# DC48V_DC24V_200W_V2_0.net
KiCad netlist of a schematic drawn in Altium Designer
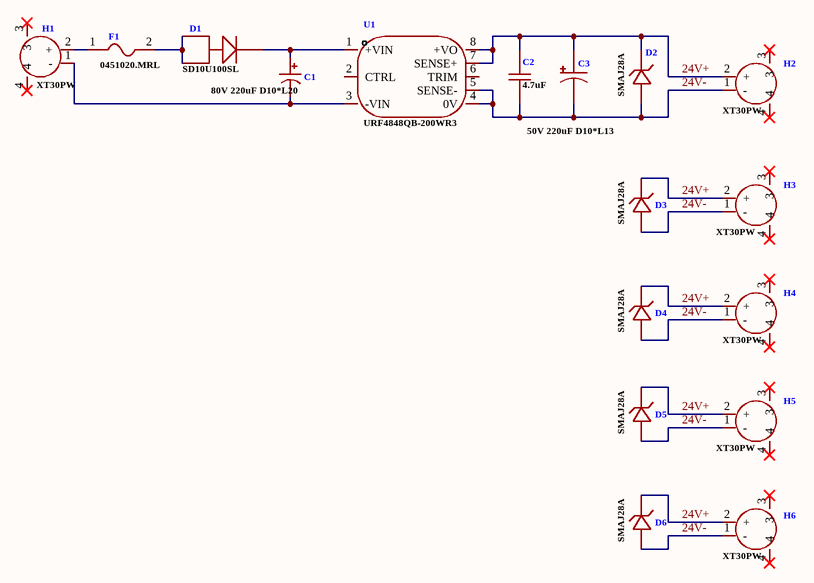
[diagram p0: DC48V_DC24V_200W_V2.0.SchDoc]

(export (version "E")
  (design (tool "Eeschema 10.0.6"))
  (components
    (comp (ref "C1")
      (value "80V 220uF D10*L20")
      (footprint "CAP-TH_BD10.0-P5.00-D1.0-FD-WL")
      (fields
        (field (name "MANUFACTURER") "AISHI(艾华集团)")
        (field (name "MANUFACTURER PART") "ERF1BM221G20OT")
        (field (name "TOLERANCE") "±20%")
      )
      (libsource (lib "电容") (part "ERF1BM221G20OT"))
    )
    (comp (ref "C2")
      (value "4.7uF")
      (footprint "1210_C")
      (description "100V 4.7uf 1210")
      (fields (field (name "MANUFACTURER") "FH(风华)") (field (name "MANUFACTURER PART") "1210B475K101NT"))
      (libsource (lib "Schlib1") (part "1210 4.7uf"))
    )
    (comp (ref "C3")
      (value "50V 220uF D10*L13")
      (footprint "CAP-TH_BD10.0-P5.00-D1.0-FD")
      (fields
        (field (name "MANUFACTURER") "AISHI(艾华集团)")
        (field (name "MANUFACTURER PART") "ERS1HM221G13OT")
        (field (name "TOLERANCE") "±20%")
      )
      (libsource (lib "电容") (part "ERS1HM221G13OT"))
    )
    (comp (ref "D1")
      (value "SD10U100SL")
      (footprint "TO-227B-SMD_L6.1-W4.3-LS7.0-RD")
      (fields (field (name "MANUFACTURER") "LGE(鲁光)"))
      (libsource (lib "二极管稳压等") (part "SD10U100SL"))
    )
    (comp (ref "D2")
      (value "SMAJ28A")
      (footprint "SMA_L4.4-W2.8-LS5.4-RD")
      (fields (field (name "MANUFACTURER") "Littelfuse(美国力特)"))
      (libsource (lib "二极管稳压等") (part "SMAJ28A_C148227"))
    )
    (comp (ref "D3")
      (value "SMAJ28A")
      (footprint "SMA_L4.4-W2.8-LS5.4-RD")
      (fields (field (name "MANUFACTURER") "Littelfuse(美国力特)"))
      (libsource (lib "二极管稳压等") (part "SMAJ28A_C148227"))
    )
    (comp (ref "D4")
      (value "SMAJ28A")
      (footprint "SMA_L4.4-W2.8-LS5.4-RD")
      (fields (field (name "MANUFACTURER") "Littelfuse(美国力特)"))
      (libsource (lib "二极管稳压等") (part "SMAJ28A_C148227"))
    )
    (comp (ref "D5")
      (value "SMAJ28A")
      (footprint "SMA_L4.4-W2.8-LS5.4-RD")
      (fields (field (name "MANUFACTURER") "Littelfuse(美国力特)"))
      (libsource (lib "二极管稳压等") (part "SMAJ28A_C148227"))
    )
    (comp (ref "D6")
      (value "SMAJ28A")
      (footprint "SMA_L4.4-W2.8-LS5.4-RD")
      (fields (field (name "MANUFACTURER") "Littelfuse(美国力特)"))
      (libsource (lib "二极管稳压等") (part "SMAJ28A_C148227"))
    )
    (comp (ref "F1")
      (value "0451020.MRL")
      (footprint "FUSE-SMD_L6.1-W2.7")
      (fields (field (name "MANUFACTURER") "Littelfuse(美国力特)"))
      (libsource (lib "保险") (part "0451020.MRL"))
    )
    (comp (ref "H1")
      (value "XT30PW")
      (footprint "CONN-TH_XT30PW-M")
      (fields (field (name "MANUFACTURER") "AMASS(艾迈斯)") (field (name "MANUFACTURER PART") "XT30PW-M30.G.Y"))
      (libsource (lib "Header") (part "XT30PW-M30.G.Y"))
    )
    (comp (ref "H2")
      (value "XT30PW")
      (footprint "CONN-TH_XT30PW-M")
      (fields (field (name "MANUFACTURER") "AMASS(艾迈斯)") (field (name "MANUFACTURER PART") "XT30PW-M30.G.Y"))
      (libsource (lib "Header") (part "XT30PW-M30.G.Y"))
    )
    (comp (ref "H3")
      (value "XT30PW")
      (footprint "CONN-TH_XT30PW-M")
      (fields (field (name "MANUFACTURER") "AMASS(艾迈斯)") (field (name "MANUFACTURER PART") "XT30PW-M30.G.Y"))
      (libsource (lib "Header") (part "XT30PW-M30.G.Y"))
    )
    (comp (ref "H4")
      (value "XT30PW")
      (footprint "CONN-TH_XT30PW-M")
      (fields (field (name "MANUFACTURER") "AMASS(艾迈斯)") (field (name "MANUFACTURER PART") "XT30PW-M30.G.Y"))
      (libsource (lib "Header") (part "XT30PW-M30.G.Y"))
    )
    (comp (ref "H5")
      (value "XT30PW")
      (footprint "CONN-TH_XT30PW-M")
      (fields (field (name "MANUFACTURER") "AMASS(艾迈斯)") (field (name "MANUFACTURER PART") "XT30PW-M30.G.Y"))
      (libsource (lib "Header") (part "XT30PW-M30.G.Y"))
    )
    (comp (ref "H6")
      (value "XT30PW")
      (footprint "CONN-TH_XT30PW-M")
      (fields (field (name "MANUFACTURER") "AMASS(艾迈斯)") (field (name "MANUFACTURER PART") "XT30PW-M30.G.Y"))
      (libsource (lib "Header") (part "XT30PW-M30.G.Y"))
    )
    (comp (ref "U1")
      (value "URF4848QB-200WR3")
      (footprint "PWRM-TH_URF48XXQB-200WR3")
      (fields (field (name "MANUFACTURER") "MORNSUN(金升阳)"))
      (libsource (lib "电源及控制") (part "URF4848QB-200WR3"))
    )
  )
  (nets
    (net (code "1") (name "/24V+") (class "Default")
      (node (ref "C2") (pin "2") (pinfunction "2_2") (pintype "passive"))
      (node (ref "C3") (pin "1") (pinfunction "1_1") (pintype "passive"))
      (node (ref "D2") (pin "1") (pinfunction "1_1") (pintype "passive"))
      (node (ref "D3") (pin "1") (pinfunction "1_1") (pintype "passive"))
      (node (ref "D4") (pin "1") (pinfunction "1_1") (pintype "passive"))
      (node (ref "D5") (pin "1") (pinfunction "1_1") (pintype "passive"))
      (node (ref "D6") (pin "1") (pinfunction "1_1") (pintype "passive"))
      (node (ref "H2") (pin "2") (pinfunction "+_2") (pintype "passive"))
      (node (ref "H3") (pin "2") (pinfunction "+_2") (pintype "passive"))
      (node (ref "H4") (pin "2") (pinfunction "+_2") (pintype "passive"))
      (node (ref "H5") (pin "2") (pinfunction "+_2") (pintype "passive"))
      (node (ref "H6") (pin "2") (pinfunction "+_2") (pintype "passive"))
      (node (ref "U1") (pin "7") (pinfunction "SENSE+_7") (pintype "passive"))
      (node (ref "U1") (pin "8") (pinfunction "+VO_8") (pintype "passive"))
    )
    (net (code "2") (name "/24V-") (class "Default")
      (node (ref "C2") (pin "1") (pinfunction "1_1") (pintype "passive"))
      (node (ref "C3") (pin "2") (pinfunction "2_2") (pintype "passive"))
      (node (ref "D2") (pin "2") (pinfunction "2_2") (pintype "passive"))
      (node (ref "D3") (pin "2") (pinfunction "2_2") (pintype "passive"))
      (node (ref "D4") (pin "2") (pinfunction "2_2") (pintype "passive"))
      (node (ref "D5") (pin "2") (pinfunction "2_2") (pintype "passive"))
      (node (ref "D6") (pin "2") (pinfunction "2_2") (pintype "passive"))
      (node (ref "H2") (pin "1") (pinfunction "-_1") (pintype "passive"))
      (node (ref "H3") (pin "1") (pinfunction "-_1") (pintype "passive"))
      (node (ref "H4") (pin "1") (pinfunction "-_1") (pintype "passive"))
      (node (ref "H5") (pin "1") (pinfunction "-_1") (pintype "passive"))
      (node (ref "H6") (pin "1") (pinfunction "-_1") (pintype "passive"))
      (node (ref "U1") (pin "4") (pinfunction "0V_4") (pintype "passive"))
      (node (ref "U1") (pin "5") (pinfunction "SENSE-_5") (pintype "passive"))
    )
    (net (code "3") (name "Net-(D1-Pad1)") (class "Default")
      (node (ref "D1") (pin "1") (pinfunction "1_1") (pintype "passive"))
      (node (ref "D1") (pin "2") (pinfunction "2_2") (pintype "passive"))
      (node (ref "F1") (pin "2") (pinfunction "2_2") (pintype "passive"))
    )
    (net (code "4") (name "Net-(H1-+)") (class "Default")
      (node (ref "F1") (pin "1") (pinfunction "1_1") (pintype "passive"))
      (node (ref "H1") (pin "2") (pinfunction "+_2") (pintype "passive"))
    )
    (net (code "5") (name "Net-(H1--)") (class "Default")
      (node (ref "C1") (pin "2") (pinfunction "2_2") (pintype "passive"))
      (node (ref "H1") (pin "1") (pinfunction "-_1") (pintype "passive"))
      (node (ref "U1") (pin "3") (pinfunction "-VIN_3") (pintype "passive"))
    )
    (net (code "6") (name "Net-(U1-+VIN)") (class "Default")
      (node (ref "C1") (pin "1") (pinfunction "1_1") (pintype "passive"))
      (node (ref "D1") (pin "3") (pinfunction "3_3") (pintype "passive"))
      (node (ref "U1") (pin "1") (pinfunction "+VIN_1") (pintype "passive"))
    )
    (net (code "7") (name "unconnected-(H1-Pad3)") (class "Default")
      (node (ref "H1") (pin "3") (pinfunction "3_3") (pintype "passive+no_connect"))
    )
    (net (code "8") (name "unconnected-(H1-Pad4)") (class "Default")
      (node (ref "H1") (pin "4") (pinfunction "4_4") (pintype "passive+no_connect"))
    )
    (net (code "9") (name "unconnected-(H2-Pad3)") (class "Default")
      (node (ref "H2") (pin "3") (pinfunction "3_3") (pintype "passive+no_connect"))
    )
    (net (code "10") (name "unconnected-(H2-Pad4)") (class "Default")
      (node (ref "H2") (pin "4") (pinfunction "4_4") (pintype "passive+no_connect"))
    )
    (net (code "11") (name "unconnected-(H3-Pad3)") (class "Default")
      (node (ref "H3") (pin "3") (pinfunction "3_3") (pintype "passive+no_connect"))
    )
    (net (code "12") (name "unconnected-(H3-Pad4)") (class "Default")
      (node (ref "H3") (pin "4") (pinfunction "4_4") (pintype "passive+no_connect"))
    )
    (net (code "13") (name "unconnected-(H4-Pad3)") (class "Default")
      (node (ref "H4") (pin "3") (pinfunction "3_3") (pintype "passive+no_connect"))
    )
    (net (code "14") (name "unconnected-(H4-Pad4)") (class "Default")
      (node (ref "H4") (pin "4") (pinfunction "4_4") (pintype "passive+no_connect"))
    )
    (net (code "15") (name "unconnected-(H5-Pad3)") (class "Default")
      (node (ref "H5") (pin "3") (pinfunction "3_3") (pintype "passive+no_connect"))
    )
    (net (code "16") (name "unconnected-(H5-Pad4)") (class "Default")
      (node (ref "H5") (pin "4") (pinfunction "4_4") (pintype "passive+no_connect"))
    )
    (net (code "17") (name "unconnected-(H6-Pad3)") (class "Default")
      (node (ref "H6") (pin "3") (pinfunction "3_3") (pintype "passive+no_connect"))
    )
    (net (code "18") (name "unconnected-(H6-Pad4)") (class "Default")
      (node (ref "H6") (pin "4") (pinfunction "4_4") (pintype "passive+no_connect"))
    )
    (net (code "19") (name "unconnected-(U1-CTRL-Pad2)") (class "Default")
      (node (ref "U1") (pin "2") (pinfunction "CTRL_2") (pintype "passive"))
    )
    (net (code "20") (name "unconnected-(U1-TRIM-Pad6)") (class "Default")
      (node (ref "U1") (pin "6") (pinfunction "TRIM_6") (pintype "passive"))
    )
  )
)
